# PortBreakoutCapacitive_r2_no_user.net
KiCad netlist of a schematic drawn in EAGLE
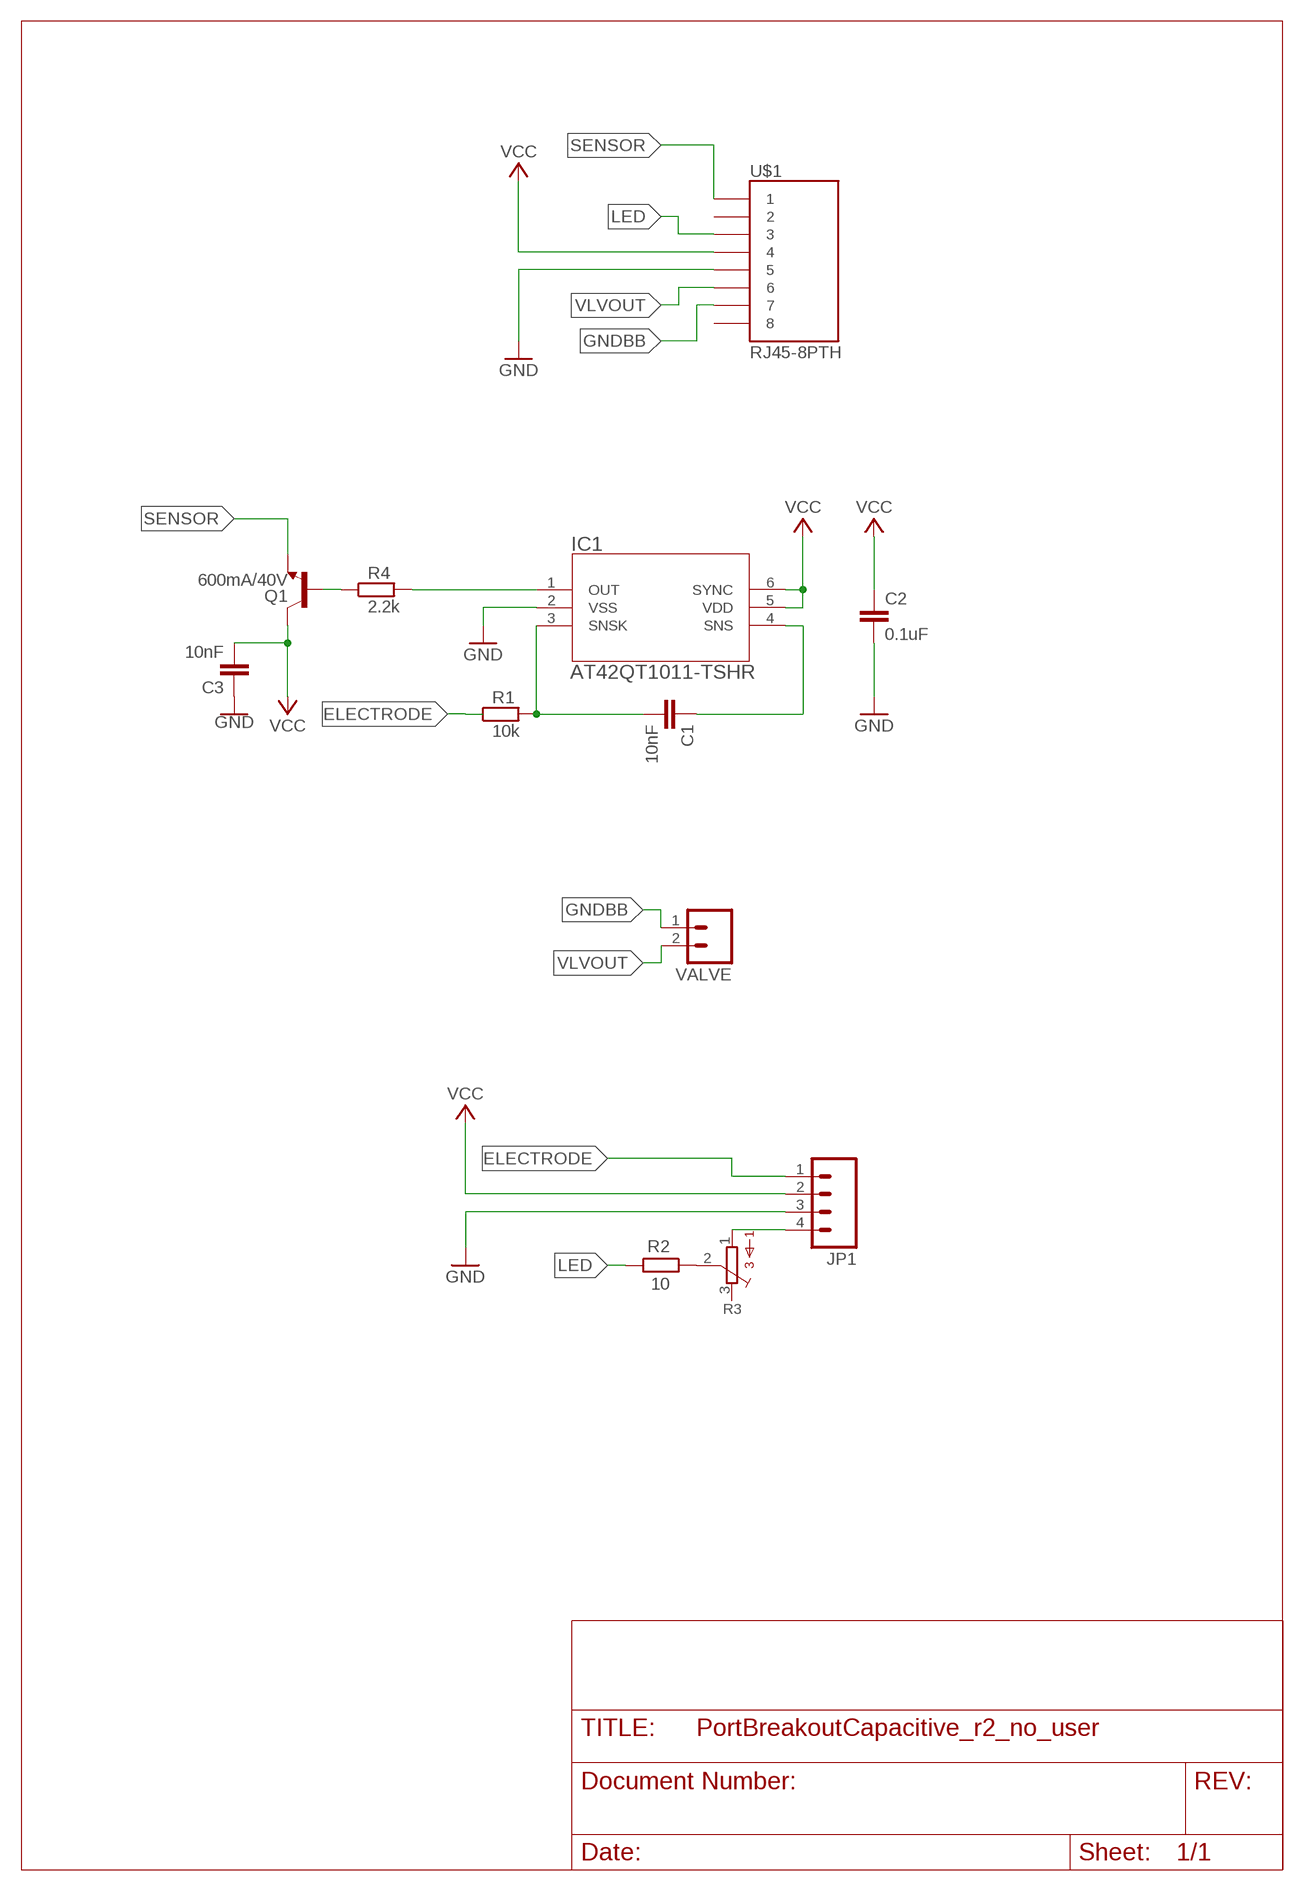
[diagram p0: schematic, sheet 1]

(export (version "E")
  (design (tool "Eeschema 10.0.6"))
  (components
    (comp (ref "C1")
      (value "10nF")
      (footprint "eagle-import:C1206")
      (libsource (lib "eagle-import") (part "C-EUC1206"))
    )
    (comp (ref "C2")
      (value "0.1uF")
      (footprint "eagle-import:C1206")
      (libsource (lib "eagle-import") (part "C-EUC1206"))
    )
    (comp (ref "C3")
      (value "10nF")
      (footprint "eagle-import:C1206")
      (libsource (lib "eagle-import") (part "C-EUC1206"))
    )
    (comp (ref "IC1")
      (value "AT42QT1011-TSHR")
      (footprint "eagle-import:6ST1_ATM")
      (fields (field (name "MANUFACTURER_PART_NUMBER") "AT42QT1010-TSHR"))
      (libsource (lib "eagle-import") (part "AT42QT1010-TSHR"))
    )
    (comp (ref "JP1")
      (value "CONN_04SCREW")
      (footprint "eagle-import:SCREWTERMINAL-3.5MM-4")
      (libsource (lib "eagle-import") (part "CONN_04SCREW"))
    )
    (comp (ref "Q1")
      (value "600mA/40V")
      (footprint "eagle-import:SOT23-3")
      (libsource (lib "eagle-import") (part "TRANS_NPN-MMBT2222AL"))
    )
    (comp (ref "R1")
      (value "10k")
      (footprint "eagle-import:R1206")
      (libsource (lib "eagle-import") (part "R-EU_R1206"))
    )
    (comp (ref "R2")
      (value "10")
      (footprint "eagle-import:R1206")
      (libsource (lib "eagle-import") (part "R-EU_R1206"))
    )
    (comp (ref "R3")
      (value "3362R")
      (footprint "eagle-import:3362R")
      (libsource (lib "eagle-import") (part "3362R"))
    )
    (comp (ref "R4")
      (value "2.2k")
      (footprint "eagle-import:R1206")
      (libsource (lib "eagle-import") (part "R-EU_R1206"))
    )
    (comp (ref "U$1")
      (value "RJ45-8PTH")
      (footprint "eagle-import:RJ45-8")
      (libsource (lib "eagle-import") (part "RJ45-8PTH"))
    )
    (comp (ref "VALVE")
      (value "M023.5MM_LOCK")
      (footprint "eagle-import:SCREWTERMINAL-3.5MM-2_LOCK")
      (libsource (lib "eagle-import") (part "M023.5MM_LOCK"))
    )
  )
  (nets
    (net (code "1") (name "ELECTRODE") (class "Default")
      (node (ref "JP1") (pin "1") (pinfunction "1_1") (pintype "passive"))
      (node (ref "R1") (pin "1") (pinfunction "1_1") (pintype "passive"))
    )
    (net (code "2") (name "GND") (class "Default")
      (node (ref "C2") (pin "2") (pinfunction "2_2") (pintype "passive"))
      (node (ref "C3") (pin "1") (pinfunction "1_1") (pintype "passive"))
      (node (ref "IC1") (pin "2") (pinfunction "VSS_2") (pintype "power_in"))
      (node (ref "JP1") (pin "3") (pinfunction "3_3") (pintype "passive"))
      (node (ref "U$1") (pin "5") (pinfunction "5_5") (pintype "bidirectional"))
    )
    (net (code "3") (name "GNDBB") (class "Default")
      (node (ref "U$1") (pin "7") (pinfunction "7_7") (pintype "bidirectional"))
      (node (ref "VALVE") (pin "1") (pinfunction "1_1") (pintype "passive"))
    )
    (net (code "4") (name "LED") (class "Default")
      (node (ref "R2") (pin "2") (pinfunction "2_2") (pintype "passive"))
      (node (ref "U$1") (pin "3") (pinfunction "3_3") (pintype "bidirectional"))
    )
    (net (code "5") (name "Net-(IC1-OUT)") (class "Default")
      (node (ref "IC1") (pin "1") (pinfunction "OUT_1") (pintype "output"))
      (node (ref "R4") (pin "2") (pinfunction "2_2") (pintype "passive"))
    )
    (net (code "6") (name "Net-(IC1-SNS)") (class "Default")
      (node (ref "C1") (pin "1") (pinfunction "1_1") (pintype "passive"))
      (node (ref "IC1") (pin "4") (pinfunction "SNS_4") (pintype "bidirectional"))
    )
    (net (code "7") (name "Net-(IC1-SNSK)") (class "Default")
      (node (ref "C1") (pin "2") (pinfunction "2_2") (pintype "passive"))
      (node (ref "IC1") (pin "3") (pinfunction "SNSK_3") (pintype "bidirectional"))
      (node (ref "R1") (pin "2") (pinfunction "2_2") (pintype "passive"))
    )
    (net (code "8") (name "Net-(JP1-Pad4)") (class "Default")
      (node (ref "JP1") (pin "4") (pinfunction "4_4") (pintype "passive"))
      (node (ref "R3") (pin "1") (pinfunction "1_1") (pintype "passive"))
    )
    (net (code "9") (name "Net-(Q1-B)") (class "Default")
      (node (ref "Q1") (pin "1") (pinfunction "B_1") (pintype "passive"))
      (node (ref "R4") (pin "1") (pinfunction "1_1") (pintype "passive"))
    )
    (net (code "10") (name "Net-(R2-Pad1)") (class "Default")
      (node (ref "R2") (pin "1") (pinfunction "1_1") (pintype "passive"))
      (node (ref "R3") (pin "2") (pinfunction "2_2") (pintype "passive"))
    )
    (net (code "11") (name "SENSOR") (class "Default")
      (node (ref "Q1") (pin "2") (pinfunction "E_2") (pintype "passive"))
      (node (ref "U$1") (pin "1") (pinfunction "1_1") (pintype "bidirectional"))
    )
    (net (code "12") (name "VCC") (class "Default")
      (node (ref "C2") (pin "1") (pinfunction "1_1") (pintype "passive"))
      (node (ref "C3") (pin "2") (pinfunction "2_2") (pintype "passive"))
      (node (ref "IC1") (pin "5") (pinfunction "VDD_5") (pintype "power_in"))
      (node (ref "IC1") (pin "6") (pinfunction "SYNC_6") (pintype "input"))
      (node (ref "JP1") (pin "2") (pinfunction "2_2") (pintype "passive"))
      (node (ref "Q1") (pin "3") (pinfunction "C_3") (pintype "passive"))
      (node (ref "U$1") (pin "4") (pinfunction "4_4") (pintype "bidirectional"))
    )
    (net (code "13") (name "VLVOUT") (class "Default")
      (node (ref "U$1") (pin "6") (pinfunction "6_6") (pintype "bidirectional"))
      (node (ref "VALVE") (pin "2") (pinfunction "2_2") (pintype "passive"))
    )
    (net (code "14") (name "unconnected-(R3-Pad3)") (class "Default")
      (node (ref "R3") (pin "3") (pinfunction "3_3") (pintype "passive"))
    )
    (net (code "15") (name "unconnected-(U$1-Pad2)") (class "Default")
      (node (ref "U$1") (pin "2") (pinfunction "2_2") (pintype "bidirectional"))
    )
    (net (code "16") (name "unconnected-(U$1-Pad8)") (class "Default")
      (node (ref "U$1") (pin "8") (pinfunction "8_8") (pintype "bidirectional"))
    )
  )
)
